# TC358779XBG.net
KiCad netlist of a schematic drawn in Altium Designer
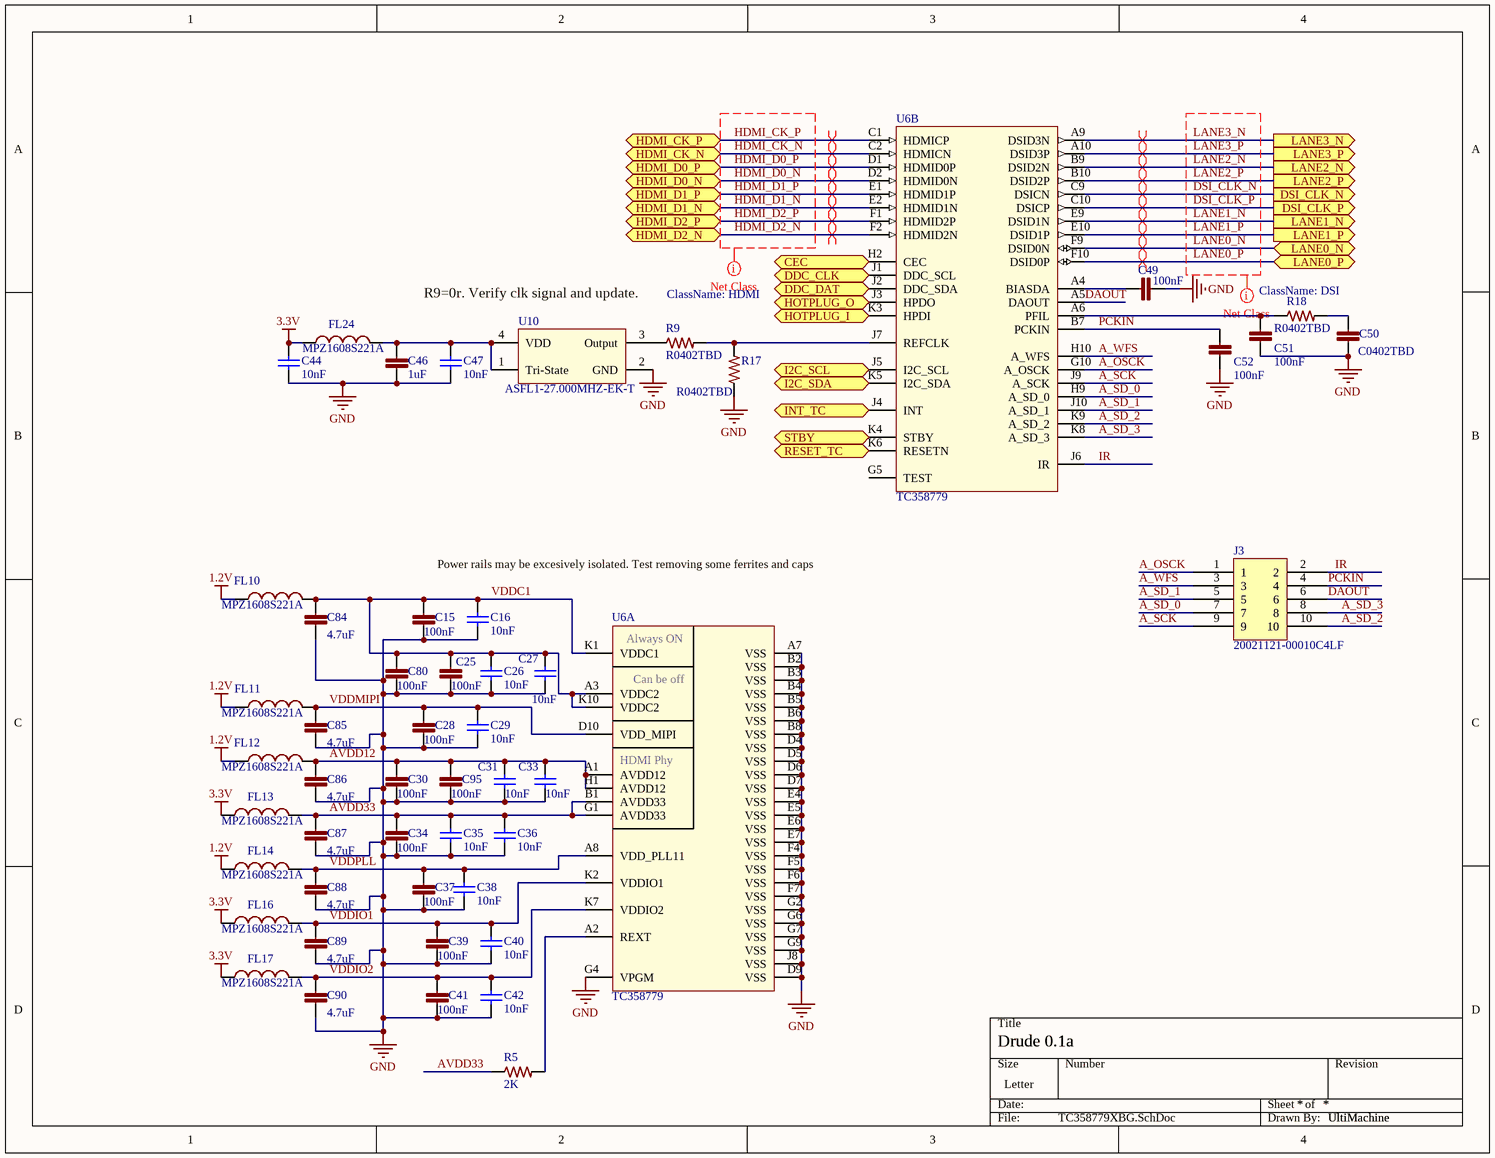
[diagram p0: TC358779XBG.SchDoc]

(export (version "E")
  (design (tool "Eeschema 10.0.6"))
  (components
    (comp (ref "C15")
      (value "100nF")
      (footprint "C0402")
      (description "CAP CER 0402 100nF 16V 10% X7R")
      (fields
        (field (name "MANUFACTURERPARTNUMBER") "GRM155R71C104KA88D")
        (field (name "PUBLISHER") "UltiMachine")
      )
      (libsource (lib "3Delight") (part "GRM155R71C104KA88D"))
    )
    (comp (ref "C16")
      (value "10nF")
      (footprint "C0402")
      (description "CAP CER 10nF 50V X7R 0402")
      (fields
        (field (name "MFR PART #") "GRM155R71H103JA88D")
        (field (name "MFR") "Murata")
        (field (name "PUBLISHER") "Ultimachine")
      )
      (libsource (lib "Tigershark3D") (part "GRM155R71H103JA88D"))
    )
    (comp (ref "C25")
      (value "100nF")
      (footprint "C0402")
      (description "CAP CER 0402 100nF 16V 10% X7R")
      (fields
        (field (name "MANUFACTURERPARTNUMBER") "GRM155R71C104KA88D")
        (field (name "PUBLISHER") "UltiMachine")
      )
      (libsource (lib "3Delight") (part "GRM155R71C104KA88D"))
    )
    (comp (ref "C26")
      (value "10nF")
      (footprint "C0402")
      (description "CAP CER 10nF 50V X7R 0402")
      (fields
        (field (name "MFR PART #") "GRM155R71H103JA88D")
        (field (name "MFR") "Murata")
        (field (name "PUBLISHER") "Ultimachine")
      )
      (libsource (lib "Tigershark3D") (part "GRM155R71H103JA88D"))
    )
    (comp (ref "C27")
      (value "10nF")
      (footprint "C0402")
      (description "CAP CER 10nF 50V X7R 0402")
      (fields
        (field (name "MFR PART #") "GRM155R71H103JA88D")
        (field (name "MFR") "Murata")
        (field (name "PUBLISHER") "Ultimachine")
      )
      (libsource (lib "Tigershark3D") (part "GRM155R71H103JA88D"))
    )
    (comp (ref "C28")
      (value "100nF")
      (footprint "C0402")
      (description "CAP CER 0402 100nF 16V 10% X7R")
      (fields
        (field (name "MANUFACTURERPARTNUMBER") "GRM155R71C104KA88D")
        (field (name "PUBLISHER") "UltiMachine")
      )
      (libsource (lib "3Delight") (part "GRM155R71C104KA88D"))
    )
    (comp (ref "C29")
      (value "10nF")
      (footprint "C0402")
      (description "CAP CER 10nF 50V X7R 0402")
      (fields
        (field (name "MFR PART #") "GRM155R71H103JA88D")
        (field (name "MFR") "Murata")
        (field (name "PUBLISHER") "Ultimachine")
      )
      (libsource (lib "Tigershark3D") (part "GRM155R71H103JA88D"))
    )
    (comp (ref "C30")
      (value "100nF")
      (footprint "C0402")
      (description "CAP CER 0402 100nF 16V 10% X7R")
      (fields
        (field (name "MANUFACTURERPARTNUMBER") "GRM155R71C104KA88D")
        (field (name "PUBLISHER") "UltiMachine")
      )
      (libsource (lib "3Delight") (part "GRM155R71C104KA88D"))
    )
    (comp (ref "C31")
      (value "10nF")
      (footprint "C0402")
      (description "CAP CER 10nF 50V X7R 0402")
      (fields
        (field (name "MFR PART #") "GRM155R71H103JA88D")
        (field (name "MFR") "Murata")
        (field (name "PUBLISHER") "Ultimachine")
      )
      (libsource (lib "Tigershark3D") (part "GRM155R71H103JA88D"))
    )
    (comp (ref "C33")
      (value "10nF")
      (footprint "C0402")
      (description "CAP CER 10nF 50V X7R 0402")
      (fields
        (field (name "MFR PART #") "GRM155R71H103JA88D")
        (field (name "MFR") "Murata")
        (field (name "PUBLISHER") "Ultimachine")
      )
      (libsource (lib "Tigershark3D") (part "GRM155R71H103JA88D"))
    )
    (comp (ref "C34")
      (value "100nF")
      (footprint "C0402")
      (description "CAP CER 0402 100nF 16V 10% X7R")
      (fields
        (field (name "MANUFACTURERPARTNUMBER") "GRM155R71C104KA88D")
        (field (name "PUBLISHER") "UltiMachine")
      )
      (libsource (lib "3Delight") (part "GRM155R71C104KA88D"))
    )
    (comp (ref "C35")
      (value "10nF")
      (footprint "C0402")
      (description "CAP CER 10nF 50V X7R 0402")
      (fields
        (field (name "MFR PART #") "GRM155R71H103JA88D")
        (field (name "MFR") "Murata")
        (field (name "PUBLISHER") "Ultimachine")
      )
      (libsource (lib "Tigershark3D") (part "GRM155R71H103JA88D"))
    )
    (comp (ref "C36")
      (value "10nF")
      (footprint "C0402")
      (description "CAP CER 10nF 50V X7R 0402")
      (fields
        (field (name "MFR PART #") "GRM155R71H103JA88D")
        (field (name "MFR") "Murata")
        (field (name "PUBLISHER") "Ultimachine")
      )
      (libsource (lib "Tigershark3D") (part "GRM155R71H103JA88D"))
    )
    (comp (ref "C37")
      (value "100nF")
      (footprint "C0402")
      (description "CAP CER 0402 100nF 16V 10% X7R")
      (fields
        (field (name "MANUFACTURERPARTNUMBER") "GRM155R71C104KA88D")
        (field (name "PUBLISHER") "UltiMachine")
      )
      (libsource (lib "3Delight") (part "GRM155R71C104KA88D"))
    )
    (comp (ref "C38")
      (value "10nF")
      (footprint "C0402")
      (description "CAP CER 10nF 50V X7R 0402")
      (fields
        (field (name "MFR PART #") "GRM155R71H103JA88D")
        (field (name "MFR") "Murata")
        (field (name "PUBLISHER") "Ultimachine")
      )
      (libsource (lib "Tigershark3D") (part "GRM155R71H103JA88D"))
    )
    (comp (ref "C39")
      (value "100nF")
      (footprint "C0402")
      (description "CAP CER 0402 100nF 16V 10% X7R")
      (fields
        (field (name "MANUFACTURERPARTNUMBER") "GRM155R71C104KA88D")
        (field (name "PUBLISHER") "UltiMachine")
      )
      (libsource (lib "3Delight") (part "GRM155R71C104KA88D"))
    )
    (comp (ref "C40")
      (value "10nF")
      (footprint "C0402")
      (description "CAP CER 10nF 50V X7R 0402")
      (fields
        (field (name "MFR PART #") "GRM155R71H103JA88D")
        (field (name "MFR") "Murata")
        (field (name "PUBLISHER") "Ultimachine")
      )
      (libsource (lib "Tigershark3D") (part "GRM155R71H103JA88D"))
    )
    (comp (ref "C41")
      (value "100nF")
      (footprint "C0402")
      (description "CAP CER 0402 100nF 16V 10% X7R")
      (fields
        (field (name "MANUFACTURERPARTNUMBER") "GRM155R71C104KA88D")
        (field (name "PUBLISHER") "UltiMachine")
      )
      (libsource (lib "3Delight") (part "GRM155R71C104KA88D"))
    )
    (comp (ref "C42")
      (value "10nF")
      (footprint "C0402")
      (description "CAP CER 10nF 50V X7R 0402")
      (fields
        (field (name "MFR PART #") "GRM155R71H103JA88D")
        (field (name "MFR") "Murata")
        (field (name "PUBLISHER") "Ultimachine")
      )
      (libsource (lib "Tigershark3D") (part "GRM155R71H103JA88D"))
    )
    (comp (ref "C44")
      (value "10nF")
      (footprint "C0402")
      (description "CAP CER 10nF 50V X7R 0402")
      (fields
        (field (name "MFR PART #") "GRM155R71H103JA88D")
        (field (name "MFR") "Murata")
        (field (name "PUBLISHER") "Ultimachine")
      )
      (libsource (lib "Tigershark3D") (part "GRM155R71H103JA88D"))
    )
    (comp (ref "C46")
      (value "1uF")
      (footprint "C0402")
      (description "CAP CER 0402 1uF 6.3V 10% X5R")
      (fields
        (field (name "MANUFACTURERPARTNUMBER") "GRM155R60J105KE19D")
        (field (name "PUBLISHER") "UltiMachine")
      )
      (libsource (lib "3Delight") (part "GRM155R60J105KE19D"))
    )
    (comp (ref "C47")
      (value "10nF")
      (footprint "C0402")
      (description "CAP CER 10nF 50V X7R 0402")
      (fields
        (field (name "MFR PART #") "GRM155R71H103JA88D")
        (field (name "MFR") "Murata")
        (field (name "PUBLISHER") "Ultimachine")
      )
      (libsource (lib "Tigershark3D") (part "GRM155R71H103JA88D"))
    )
    (comp (ref "C49")
      (value "100nF")
      (footprint "C0402")
      (description "CAP CER 0402 100nF 16V 10% X7R")
      (fields
        (field (name "MANUFACTURERPARTNUMBER") "GRM155R71C104KA88D")
        (field (name "PUBLISHER") "UltiMachine")
      )
      (libsource (lib "") (part "GRM155R71C104KA88D_1"))
    )
    (comp (ref "C50")
      (value "C0402TBD")
      (footprint "C0402")
      (description "Capacitor Non Polarized")
      (fields (field (name "PUBLISHER") "UltiMachine"))
      (libsource (lib "3Delight") (part "C0402TBD"))
    )
    (comp (ref "C51")
      (value "100nF")
      (footprint "C0402")
      (description "CAP CER 0402 100nF 16V 10% X7R")
      (fields
        (field (name "MANUFACTURERPARTNUMBER") "GRM155R71C104KA88D")
        (field (name "PUBLISHER") "UltiMachine")
      )
      (libsource (lib "3Delight") (part "GRM155R71C104KA88D"))
    )
    (comp (ref "C52")
      (value "100nF")
      (footprint "C0402")
      (description "CAP CER 0402 100nF 16V 10% X7R")
      (fields
        (field (name "MANUFACTURERPARTNUMBER") "GRM155R71C104KA88D")
        (field (name "PUBLISHER") "UltiMachine")
      )
      (libsource (lib "3Delight") (part "GRM155R71C104KA88D"))
    )
    (comp (ref "C80")
      (value "100nF")
      (footprint "C0402")
      (description "CAP CER 0402 100nF 16V 10% X7R")
      (fields
        (field (name "MANUFACTURERPARTNUMBER") "GRM155R71C104KA88D")
        (field (name "PUBLISHER") "UltiMachine")
      )
      (libsource (lib "3Delight") (part "GRM155R71C104KA88D"))
    )
    (comp (ref "C84")
      (value "4.7uF")
      (footprint "C0603")
      (description "CAP CER 4.7UF 10V X5R 0603")
      (fields
        (field (name "MANUFACTURERPARTNUMBER") "GRM188R61A475KE15D")
        (field (name "PUBLISHER") "UltiMachine")
      )
      (libsource (lib "hmi") (part "GRM188R61A475KE15D"))
    )
    (comp (ref "C85")
      (value "4.7uF")
      (footprint "C0603")
      (description "CAP CER 4.7UF 10V X5R 0603")
      (fields
        (field (name "MANUFACTURERPARTNUMBER") "GRM188R61A475KE15D")
        (field (name "PUBLISHER") "UltiMachine")
      )
      (libsource (lib "hmi") (part "GRM188R61A475KE15D"))
    )
    (comp (ref "C86")
      (value "4.7uF")
      (footprint "C0603")
      (description "CAP CER 4.7UF 10V X5R 0603")
      (fields
        (field (name "MANUFACTURERPARTNUMBER") "GRM188R61A475KE15D")
        (field (name "PUBLISHER") "UltiMachine")
      )
      (libsource (lib "hmi") (part "GRM188R61A475KE15D"))
    )
    (comp (ref "C87")
      (value "4.7uF")
      (footprint "C0603")
      (description "CAP CER 4.7UF 10V X5R 0603")
      (fields
        (field (name "MANUFACTURERPARTNUMBER") "GRM188R61A475KE15D")
        (field (name "PUBLISHER") "UltiMachine")
      )
      (libsource (lib "hmi") (part "GRM188R61A475KE15D"))
    )
    (comp (ref "C88")
      (value "4.7uF")
      (footprint "C0603")
      (description "CAP CER 4.7UF 10V X5R 0603")
      (fields
        (field (name "MANUFACTURERPARTNUMBER") "GRM188R61A475KE15D")
        (field (name "PUBLISHER") "UltiMachine")
      )
      (libsource (lib "hmi") (part "GRM188R61A475KE15D"))
    )
    (comp (ref "C89")
      (value "4.7uF")
      (footprint "C0603")
      (description "CAP CER 4.7UF 10V X5R 0603")
      (fields
        (field (name "MANUFACTURERPARTNUMBER") "GRM188R61A475KE15D")
        (field (name "PUBLISHER") "UltiMachine")
      )
      (libsource (lib "hmi") (part "GRM188R61A475KE15D"))
    )
    (comp (ref "C90")
      (value "4.7uF")
      (footprint "C0603")
      (description "CAP CER 4.7UF 10V X5R 0603")
      (fields
        (field (name "MANUFACTURERPARTNUMBER") "GRM188R61A475KE15D")
        (field (name "PUBLISHER") "UltiMachine")
      )
      (libsource (lib "hmi") (part "GRM188R61A475KE15D"))
    )
    (comp (ref "C95")
      (value "100nF")
      (footprint "C0402")
      (description "CAP CER 0402 100nF 16V 10% X7R")
      (fields
        (field (name "MANUFACTURERPARTNUMBER") "GRM155R71C104KA88D")
        (field (name "PUBLISHER") "UltiMachine")
      )
      (libsource (lib "3Delight") (part "GRM155R71C104KA88D"))
    )
    (comp (ref "FL10")
      (value "MPZ1608S221A")
      (footprint "C0603")
      (description "Ferrite")
      (fields (field (name "PUBLISHER") "UltiMachine"))
      (libsource (lib "3Delight") (part "MPZ1608S221A"))
    )
    (comp (ref "FL11")
      (value "MPZ1608S221A")
      (footprint "C0603")
      (description "Ferrite")
      (fields (field (name "PUBLISHER") "UltiMachine"))
      (libsource (lib "3Delight") (part "MPZ1608S221A"))
    )
    (comp (ref "FL12")
      (value "MPZ1608S221A")
      (footprint "C0603")
      (description "Ferrite")
      (fields (field (name "PUBLISHER") "UltiMachine"))
      (libsource (lib "3Delight") (part "MPZ1608S221A"))
    )
    (comp (ref "FL13")
      (value "MPZ1608S221A")
      (footprint "C0603")
      (description "Ferrite")
      (fields (field (name "PUBLISHER") "UltiMachine"))
      (libsource (lib "3Delight") (part "MPZ1608S221A"))
    )
    (comp (ref "FL14")
      (value "MPZ1608S221A")
      (footprint "C0603")
      (description "Ferrite")
      (fields (field (name "PUBLISHER") "UltiMachine"))
      (libsource (lib "3Delight") (part "MPZ1608S221A"))
    )
    (comp (ref "FL16")
      (value "MPZ1608S221A")
      (footprint "C0603")
      (description "Ferrite")
      (fields (field (name "PUBLISHER") "UltiMachine"))
      (libsource (lib "3Delight") (part "MPZ1608S221A"))
    )
    (comp (ref "FL17")
      (value "MPZ1608S221A")
      (footprint "C0603")
      (description "Ferrite")
      (fields (field (name "PUBLISHER") "UltiMachine"))
      (libsource (lib "3Delight") (part "MPZ1608S221A"))
    )
    (comp (ref "FL24")
      (value "MPZ1608S221A")
      (footprint "C0603")
      (description "Ferrite")
      (fields (field (name "PUBLISHER") "UltiMachine"))
      (libsource (lib "") (part "MPZ1608S221A_1"))
    )
    (comp (ref "J3")
      (value "20021121-00010C4LF")
      (footprint "FTSH-105-XX-X-DV")
      (libsource (lib "Adams Altium Library") (part "ARM Cortex JTAG-DEBUG Header"))
    )
    (comp (ref "R5")
      (value "2K")
      (footprint "R0402")
      (description "RES SMD 2K OHM 1% 1/16W 0402")
      (fields
        (field (name "MANUFACTURERPARTNUMBER") "RC0402FR-0710KP")
        (field (name "PUBLISHER") "UltiMachine")
      )
      (libsource (lib "3Delight") (part "RC0402FR-072KL"))
    )
    (comp (ref "R9")
      (value "R0402TBD")
      (footprint "R0402")
      (description "Resistor")
      (fields (field (name "PUBLISHER") "UltiMachine"))
      (libsource (lib "3Delight") (part "R0402TBD"))
    )
    (comp (ref "R17")
      (value "R0402TBD")
      (footprint "R0402")
      (description "Resistor")
      (fields (field (name "PUBLISHER") "UltiMachine"))
      (libsource (lib "3Delight") (part "R0402TBD"))
    )
    (comp (ref "R18")
      (value "R0402TBD")
      (footprint "R0402")
      (description "Resistor")
      (fields (field (name "PUBLISHER") "UltiMachine"))
      (libsource (lib "3Delight") (part "R0402TBD"))
    )
    (comp (ref "U6")
      (value "TC358779")
      (footprint "BGA80-0707-065")
      (libsource (lib "hmi") (part "TC358779"))
    )
    (comp (ref "U10")
      (value "ASFL1-27.000MHZ-EK-T")
      (footprint "OSC-5x3.2x1.3")
      (description "OSC XO 27.000MHZ HCMOS TTL SMD")
      (libsource (lib "hmi") (part "ASFL1-27.000MHZ-EK-T"))
    )
  )
  (nets
    (net (code "1") (name "/AVDD12") (class "Default")
      (node (ref "C30") (pin "1") (pinfunction "1_1") (pintype "passive"))
      (node (ref "C31") (pin "2") (pinfunction "2_2") (pintype "passive"))
      (node (ref "C33") (pin "2") (pinfunction "2_2") (pintype "passive"))
      (node (ref "C86") (pin "1") (pinfunction "1_1") (pintype "passive"))
      (node (ref "C95") (pin "1") (pinfunction "1_1") (pintype "passive"))
      (node (ref "FL12") (pin "2") (pinfunction "2_2") (pintype "passive"))
      (node (ref "U6") (pin "A1") (pinfunction "AVDD12_A1") (pintype "power_in"))
      (node (ref "U6") (pin "H1") (pinfunction "AVDD12_H1") (pintype "power_in"))
    )
    (net (code "2") (name "/AVDD33") (class "Default")
      (node (ref "C34") (pin "1") (pinfunction "1_1") (pintype "passive"))
      (node (ref "C35") (pin "2") (pinfunction "2_2") (pintype "passive"))
      (node (ref "C36") (pin "2") (pinfunction "2_2") (pintype "passive"))
      (node (ref "C87") (pin "1") (pinfunction "1_1") (pintype "passive"))
      (node (ref "FL13") (pin "2") (pinfunction "2_2") (pintype "passive"))
      (node (ref "R5") (pin "1") (pinfunction "1_1") (pintype "passive"))
      (node (ref "U6") (pin "B1") (pinfunction "AVDD33_B1") (pintype "power_in"))
      (node (ref "U6") (pin "G1") (pinfunction "AVDD33_G1") (pintype "power_in"))
    )
    (net (code "3") (name "/A_OSCK") (class "Default")
      (node (ref "J3") (pin "1") (pinfunction "1_1") (pintype "passive"))
      (node (ref "U6") (pin "G10") (pinfunction "A_OSCK_G10") (pintype "power_in"))
    )
    (net (code "4") (name "/A_SCK") (class "Default")
      (node (ref "J3") (pin "9") (pinfunction "9_9") (pintype "passive"))
      (node (ref "U6") (pin "J9") (pinfunction "A_SCK_J9") (pintype "power_in"))
    )
    (net (code "5") (name "/A_SD_0") (class "Default")
      (node (ref "J3") (pin "7") (pinfunction "7_7") (pintype "passive"))
      (node (ref "U6") (pin "H9") (pinfunction "A_SD_0_H9") (pintype "power_in"))
    )
    (net (code "6") (name "/A_SD_1") (class "Default")
      (node (ref "J3") (pin "5") (pinfunction "5_5") (pintype "passive"))
      (node (ref "U6") (pin "J10") (pinfunction "A_SD_1_J10") (pintype "power_in"))
    )
    (net (code "7") (name "/A_SD_2") (class "Default")
      (node (ref "J3") (pin "10") (pinfunction "10_10") (pintype "passive"))
      (node (ref "U6") (pin "K9") (pinfunction "A_SD_2_K9") (pintype "power_in"))
    )
    (net (code "8") (name "/A_SD_3") (class "Default")
      (node (ref "J3") (pin "8") (pinfunction "8_8") (pintype "passive"))
      (node (ref "U6") (pin "K8") (pinfunction "A_SD_3_K8") (pintype "power_in"))
    )
    (net (code "9") (name "/A_WFS") (class "Default")
      (node (ref "J3") (pin "3") (pinfunction "3_3") (pintype "passive"))
      (node (ref "U6") (pin "H10") (pinfunction "A_WFS_H10") (pintype "power_in"))
    )
    (net (code "10") (name "/CEC") (class "Default")
      (node (ref "U6") (pin "H2") (pinfunction "CEC_H2") (pintype "power_in"))
    )
    (net (code "11") (name "/DAOUT") (class "Default")
      (node (ref "J3") (pin "6") (pinfunction "6_6") (pintype "passive"))
      (node (ref "U6") (pin "A5") (pinfunction "DAOUT_A5") (pintype "power_in"))
    )
    (net (code "12") (name "/DDC_CLK") (class "Default")
      (node (ref "U6") (pin "J1") (pinfunction "DDC_SCL_J1") (pintype "power_in"))
    )
    (net (code "13") (name "/DDC_DAT") (class "Default")
      (node (ref "U6") (pin "J2") (pinfunction "DDC_SDA_J2") (pintype "power_in"))
    )
    (net (code "14") (name "/DSI_CLK_N") (class "Default")
      (node (ref "U6") (pin "C9") (pinfunction "DSICN_C9") (pintype "output"))
    )
    (net (code "15") (name "/DSI_CLK_P") (class "Default")
      (node (ref "U6") (pin "C10") (pinfunction "DSICP_C10") (pintype "output"))
    )
    (net (code "16") (name "/HDMI_CK_N") (class "Default")
      (node (ref "U6") (pin "C2") (pinfunction "HDMICN_C2") (pintype "input"))
    )
    (net (code "17") (name "/HDMI_CK_P") (class "Default")
      (node (ref "U6") (pin "C1") (pinfunction "HDMICP_C1") (pintype "input"))
    )
    (net (code "18") (name "/HDMI_D0_N") (class "Default")
      (node (ref "U6") (pin "D2") (pinfunction "HDMID0N_D2") (pintype "input"))
    )
    (net (code "19") (name "/HDMI_D0_P") (class "Default")
      (node (ref "U6") (pin "D1") (pinfunction "HDMID0P_D1") (pintype "input"))
    )
    (net (code "20") (name "/HDMI_D1_N") (class "Default")
      (node (ref "U6") (pin "E2") (pinfunction "HDMID1N_E2") (pintype "input"))
    )
    (net (code "21") (name "/HDMI_D1_P") (class "Default")
      (node (ref "U6") (pin "E1") (pinfunction "HDMID1P_E1") (pintype "input"))
    )
    (net (code "22") (name "/HDMI_D2_N") (class "Default")
      (node (ref "U6") (pin "F2") (pinfunction "HDMID2N_F2") (pintype "input"))
    )
    (net (code "23") (name "/HDMI_D2_P") (class "Default")
      (node (ref "U6") (pin "F1") (pinfunction "HDMID2P_F1") (pintype "input"))
    )
    (net (code "24") (name "/HOTPLUG_I") (class "Default")
      (node (ref "U6") (pin "K3") (pinfunction "HPDI_K3") (pintype "power_in"))
    )
    (net (code "25") (name "/HOTPLUG_O") (class "Default")
      (node (ref "U6") (pin "J3") (pinfunction "HPDO_J3") (pintype "power_in"))
    )
    (net (code "26") (name "/I2C_SCL") (class "Default")
      (node (ref "U6") (pin "J5") (pinfunction "I2C_SCL_J5") (pintype "power_in"))
    )
    (net (code "27") (name "/I2C_SDA") (class "Default")
      (node (ref "U6") (pin "K5") (pinfunction "I2C_SDA_K5") (pintype "power_in"))
    )
    (net (code "28") (name "/INT_TC") (class "Default")
      (node (ref "U6") (pin "J4") (pinfunction "INT_J4") (pintype "power_in"))
    )
    (net (code "29") (name "/IR") (class "Default")
      (node (ref "J3") (pin "2") (pinfunction "2_2") (pintype "passive"))
      (node (ref "U6") (pin "J6") (pinfunction "IR_J6") (pintype "power_in"))
    )
    (net (code "30") (name "/LANE0_N") (class "Default")
      (node (ref "U6") (pin "F9") (pinfunction "DSID0N_F9") (pintype "bidirectional"))
    )
    (net (code "31") (name "/LANE0_P") (class "Default")
      (node (ref "U6") (pin "F10") (pinfunction "DSID0P_F10") (pintype "bidirectional"))
    )
    (net (code "32") (name "/LANE1_N") (class "Default")
      (node (ref "U6") (pin "E9") (pinfunction "DSID1N_E9") (pintype "output"))
    )
    (net (code "33") (name "/LANE1_P") (class "Default")
      (node (ref "U6") (pin "E10") (pinfunction "DSID1P_E10") (pintype "output"))
    )
    (net (code "34") (name "/LANE2_N") (class "Default")
      (node (ref "U6") (pin "B9") (pinfunction "DSID2N_B9") (pintype "output"))
    )
    (net (code "35") (name "/LANE2_P") (class "Default")
      (node (ref "U6") (pin "B10") (pinfunction "DSID2P_B10") (pintype "output"))
    )
    (net (code "36") (name "/LANE3_N") (class "Default")
      (node (ref "U6") (pin "A9") (pinfunction "DSID3N_A9") (pintype "output"))
    )
    (net (code "37") (name "/LANE3_P") (class "Default")
      (node (ref "U6") (pin "A10") (pinfunction "DSID3P_A10") (pintype "output"))
    )
    (net (code "38") (name "/PCKIN") (class "Default")
      (node (ref "C52") (pin "1") (pinfunction "1_1") (pintype "passive"))
      (node (ref "J3") (pin "4") (pinfunction "4_4") (pintype "passive"))
      (node (ref "U6") (pin "B7") (pinfunction "PCKIN_B7") (pintype "power_in"))
    )
    (net (code "39") (name "/RESET_TC") (class "Default")
      (node (ref "U6") (pin "K6") (pinfunction "RESETN_K6") (pintype "power_in"))
    )
    (net (code "40") (name "/STBY") (class "Default")
      (node (ref "U6") (pin "K4") (pinfunction "STBY_K4") (pintype "power_in"))
    )
    (net (code "41") (name "/VDDC1") (class "Default")
      (node (ref "C15") (pin "1") (pinfunction "1_1") (pintype "passive"))
      (node (ref "C16") (pin "2") (pinfunction "2_2") (pintype "passive"))
      (node (ref "C25") (pin "1") (pinfunction "1_1") (pintype "passive"))
      (node (ref "C26") (pin "2") (pinfunction "2_2") (pintype "passive"))
      (node (ref "C27") (pin "2") (pinfunction "2_2") (pintype "passive"))
      (node (ref "C80") (pin "1") (pinfunction "1_1") (pintype "passive"))
      (node (ref "C84") (pin "1") (pinfunction "1_1") (pintype "passive"))
      (node (ref "FL10") (pin "2") (pinfunction "2_2") (pintype "passive"))
      (node (ref "U6") (pin "A3") (pinfunction "VDDC2_A3") (pintype "power_in"))
      (node (ref "U6") (pin "K1") (pinfunction "VDDC1_K1") (pintype "power_in"))
      (node (ref "U6") (pin "K10") (pinfunction "VDDC2_K10") (pintype "power_in"))
    )
    (net (code "42") (name "/VDDIO1") (class "Default")
      (node (ref "C39") (pin "1") (pinfunction "1_1") (pintype "passive"))
      (node (ref "C40") (pin "2") (pinfunction "2_2") (pintype "passive"))
      (node (ref "C89") (pin "1") (pinfunction "1_1") (pintype "passive"))
      (node (ref "FL16") (pin "2") (pinfunction "2_2") (pintype "passive"))
      (node (ref "U6") (pin "K2") (pinfunction "VDDIO1_K2") (pintype "power_in"))
    )
    (net (code "43") (name "/VDDIO2") (class "Default")
      (node (ref "C41") (pin "1") (pinfunction "1_1") (pintype "passive"))
      (node (ref "C42") (pin "2") (pinfunction "2_2") (pintype "passive"))
      (node (ref "C90") (pin "1") (pinfunction "1_1") (pintype "passive"))
      (node (ref "FL17") (pin "2") (pinfunction "2_2") (pintype "passive"))
      (node (ref "U6") (pin "K7") (pinfunction "VDDIO2_K7") (pintype "power_in"))
    )
    (net (code "44") (name "/VDDMIPI") (class "Default")
      (node (ref "C28") (pin "1") (pinfunction "1_1") (pintype "passive"))
      (node (ref "C29") (pin "2") (pinfunction "2_2") (pintype "passive"))
      (node (ref "C85") (pin "1") (pinfunction "1_1") (pintype "passive"))
      (node (ref "FL11") (pin "2") (pinfunction "2_2") (pintype "passive"))
      (node (ref "U6") (pin "D10") (pinfunction "VDD_MIPI_D10") (pintype "power_in"))
    )
    (net (code "45") (name "/VDDPLL") (class "Default")
      (node (ref "C37") (pin "1") (pinfunction "1_1") (pintype "passive"))
      (node (ref "C38") (pin "2") (pinfunction "2_2") (pintype "passive"))
      (node (ref "C88") (pin "1") (pinfunction "1_1") (pintype "passive"))
      (node (ref "FL14") (pin "2") (pinfunction "2_2") (pintype "passive"))
      (node (ref "U6") (pin "A8") (pinfunction "VDD_PLL11_A8") (pintype "power_in"))
    )
    (net (code "46") (name "1.2V") (class "Default")
      (node (ref "FL10") (pin "1") (pinfunction "1_1") (pintype "passive"))
      (node (ref "FL11") (pin "1") (pinfunction "1_1") (pintype "passive"))
      (node (ref "FL12") (pin "1") (pinfunction "1_1") (pintype "passive"))
      (node (ref "FL14") (pin "1") (pinfunction "1_1") (pintype "passive"))
    )
    (net (code "47") (name "3.3V") (class "Default")
      (node (ref "C44") (pin "2") (pinfunction "2_2") (pintype "passive"))
      (node (ref "FL13") (pin "1") (pinfunction "1_1") (pintype "passive"))
      (node (ref "FL16") (pin "1") (pinfunction "1_1") (pintype "passive"))
      (node (ref "FL17") (pin "1") (pinfunction "1_1") (pintype "passive"))
      (node (ref "FL24") (pin "2") (pinfunction "2_2") (pintype "passive"))
    )
    (net (code "48") (name "GND") (class "Default")
      (node (ref "C15") (pin "2") (pinfunction "2_2") (pintype "passive"))
      (node (ref "C16") (pin "1") (pinfunction "1_1") (pintype "passive"))
      (node (ref "C25") (pin "2") (pinfunction "2_2") (pintype "passive"))
      (node (ref "C26") (pin "1") (pinfunction "1_1") (pintype "passive"))
      (node (ref "C27") (pin "1") (pinfunction "1_1") (pintype "passive"))
      (node (ref "C28") (pin "2") (pinfunction "2_2") (pintype "passive"))
      (node (ref "C29") (pin "1") (pinfunction "1_1") (pintype "passive"))
      (node (ref "C30") (pin "2") (pinfunction "2_2") (pintype "passive"))
      (node (ref "C31") (pin "1") (pinfunction "1_1") (pintype "passive"))
      (node (ref "C33") (pin "1") (pinfunction "1_1") (pintype "passive"))
      (node (ref "C34") (pin "2") (pinfunction "2_2") (pintype "passive"))
      (node (ref "C35") (pin "1") (pinfunction "1_1") (pintype "passive"))
      (node (ref "C36") (pin "1") (pinfunction "1_1") (pintype "passive"))
      (node (ref "C37") (pin "2") (pinfunction "2_2") (pintype "passive"))
      (node (ref "C38") (pin "1") (pinfunction "1_1") (pintype "passive"))
      (node (ref "C39") (pin "2") (pinfunction "2_2") (pintype "passive"))
      (node (ref "C40") (pin "1") (pinfunction "1_1") (pintype "passive"))
      (node (ref "C41") (pin "2") (pinfunction "2_2") (pintype "passive"))
      (node (ref "C42") (pin "1") (pinfunction "1_1") (pintype "passive"))
      (node (ref "C44") (pin "1") (pinfunction "1_1") (pintype "passive"))
      (node (ref "C46") (pin "2") (pinfunction "2_2") (pintype "passive"))
      (node (ref "C47") (pin "1") (pinfunction "1_1") (pintype "passive"))
      (node (ref "C49") (pin "2") (pinfunction "2_2") (pintype "passive"))
      (node (ref "C50") (pin "2") (pinfunction "2_2") (pintype "passive"))
      (node (ref "C51") (pin "2") (pinfunction "2_2") (pintype "passive"))
      (node (ref "C52") (pin "2") (pinfunction "2_2") (pintype "passive"))
      (node (ref "C80") (pin "2") (pinfunction "2_2") (pintype "passive"))
      (node (ref "C84") (pin "2") (pinfunction "2_2") (pintype "passive"))
      (node (ref "C85") (pin "2") (pinfunction "2_2") (pintype "passive"))
      (node (ref "C86") (pin "2") (pinfunction "2_2") (pintype "passive"))
      (node (ref "C87") (pin "2") (pinfunction "2_2") (pintype "passive"))
      (node (ref "C88") (pin "2") (pinfunction "2_2") (pintype "passive"))
      (node (ref "C89") (pin "2") (pinfunction "2_2") (pintype "passive"))
      (node (ref "C90") (pin "2") (pinfunction "2_2") (pintype "passive"))
      (node (ref "C95") (pin "2") (pinfunction "2_2") (pintype "passive"))
      (node (ref "R17") (pin "1") (pinfunction "1_1") (pintype "passive"))
      (node (ref "U10") (pin "2") (pinfunction "GND_2") (pintype "power_in"))
      (node (ref "U6") (pin "A7") (pinfunction "VSS_A7") (pintype "power_in"))
      (node (ref "U6") (pin "B2") (pinfunction "VSS_B2") (pintype "power_in"))
      (node (ref "U6") (pin "B3") (pinfunction "VSS_B3") (pintype "power_in"))
      (node (ref "U6") (pin "B4") (pinfunction "VSS_B4") (pintype "power_in"))
      (node (ref "U6") (pin "B5") (pinfunction "VSS_B5") (pintype "power_in"))
      (node (ref "U6") (pin "B6") (pinfunction "VSS_B6") (pintype "power_in"))
      (node (ref "U6") (pin "B8") (pinfunction "VSS_B8") (pintype "power_in"))
      (node (ref "U6") (pin "D4") (pinfunction "VSS_D4") (pintype "power_in"))
      (node (ref "U6") (pin "D5") (pinfunction "VSS_D5") (pintype "power_in"))
      (node (ref "U6") (pin "D6") (pinfunction "VSS_D6") (pintype "power_in"))
      (node (ref "U6") (pin "D7") (pinfunction "VSS_D7") (pintype "power_in"))
      (node (ref "U6") (pin "D9") (pinfunction "VSS_D9") (pintype "power_in"))
      (node (ref "U6") (pin "E4") (pinfunction "VSS_E4") (pintype "power_in"))
      (node (ref "U6") (pin "E5") (pinfunction "VSS_E5") (pintype "power_in"))
      (node (ref "U6") (pin "E6") (pinfunction "VSS_E6") (pintype "power_in"))
      (node (ref "U6") (pin "E7") (pinfunction "VSS_E7") (pintype "power_in"))
      (node (ref "U6") (pin "F4") (pinfunction "VSS_F4") (pintype "power_in"))
      (node (ref "U6") (pin "F5") (pinfunction "VSS_F5") (pintype "power_in"))
      (node (ref "U6") (pin "F6") (pinfunction "VSS_F6") (pintype "power_in"))
      (node (ref "U6") (pin "F7") (pinfunction "VSS_F7") (pintype "power_in"))
      (node (ref "U6") (pin "G2") (pinfunction "VSS_G2") (pintype "power_in"))
      (node (ref "U6") (pin "G4") (pinfunction "VPGM_G4") (pintype "power_in"))
      (node (ref "U6") (pin "G6") (pinfunction "VSS_G6") (pintype "power_in"))
      (node (ref "U6") (pin "G7") (pinfunction "VSS_G7") (pintype "power_in"))
      (node (ref "U6") (pin "G9") (pinfunction "VSS_G9") (pintype "power_in"))
      (node (ref "U6") (pin "J8") (pinfunction "VSS_J8") (pintype "power_in"))
    )
    (net (code "49") (name "Net-(C50-Pad1)") (class "Default")
      (node (ref "C50") (pin "1") (pinfunction "1_1") (pintype "passive"))
      (node (ref "R18") (pin "2") (pinfunction "2_2") (pintype "passive"))
    )
    (net (code "50") (name "Net-(U6A-REXT)") (class "Default")
      (node (ref "R5") (pin "2") (pinfunction "2_2") (pintype "passive"))
      (node (ref "U6") (pin "A2") (pinfunction "REXT_A2") (pintype "power_in"))
    )
    (net (code "51") (name "Net-(U6B-BIASDA)") (class "Default")
      (node (ref "C49") (pin "1") (pinfunction "1_1") (pintype "passive"))
      (node (ref "U6") (pin "A4") (pinfunction "BIASDA_A4") (pintype "power_in"))
    )
    (net (code "52") (name "Net-(U6B-PFIL)") (class "Default")
      (node (ref "C51") (pin "1") (pinfunction "1_1") (pintype "passive"))
      (node (ref "R18") (pin "1") (pinfunction "1_1") (pintype "passive"))
      (node (ref "U6") (pin "A6") (pinfunction "PFIL_A6") (pintype "power_in"))
    )
    (net (code "53") (name "Net-(U6B-REFCLK)") (class "Default")
      (node (ref "R17") (pin "2") (pinfunction "2_2") (pintype "passive"))
      (node (ref "R9") (pin "2") (pinfunction "2_2") (pintype "passive"))
      (node (ref "U6") (pin "J7") (pinfunction "REFCLK_J7") (pintype "power_in"))
    )
    (net (code "54") (name "Net-(U10-Output)") (class "Default")
      (node (ref "R9") (pin "1") (pinfunction "1_1") (pintype "passive"))
      (node (ref "U10") (pin "3") (pinfunction "Output_3") (pintype "power_in"))
    )
    (net (code "55") (name "Net-(U10-Tri-State)") (class "Default")
      (node (ref "C46") (pin "1") (pinfunction "1_1") (pintype "passive"))
      (node (ref "C47") (pin "2") (pinfunction "2_2") (pintype "passive"))
      (node (ref "FL24") (pin "1") (pinfunction "1_1") (pintype "passive"))
      (node (ref "U10") (pin "1") (pinfunction "Tri-State_1") (pintype "power_in"))
      (node (ref "U10") (pin "4") (pinfunction "VDD_4") (pintype "power_in"))
    )
    (net (code "56") (name "unconnected-(U6B-TEST-PadG5)") (class "Default")
      (node (ref "U6") (pin "G5") (pinfunction "TEST_G5") (pintype "power_in"))
    )
  )
)
